# UB8830_Ersatz_005_EAGLE_630.net
KiCad netlist of a schematic drawn in EAGLE
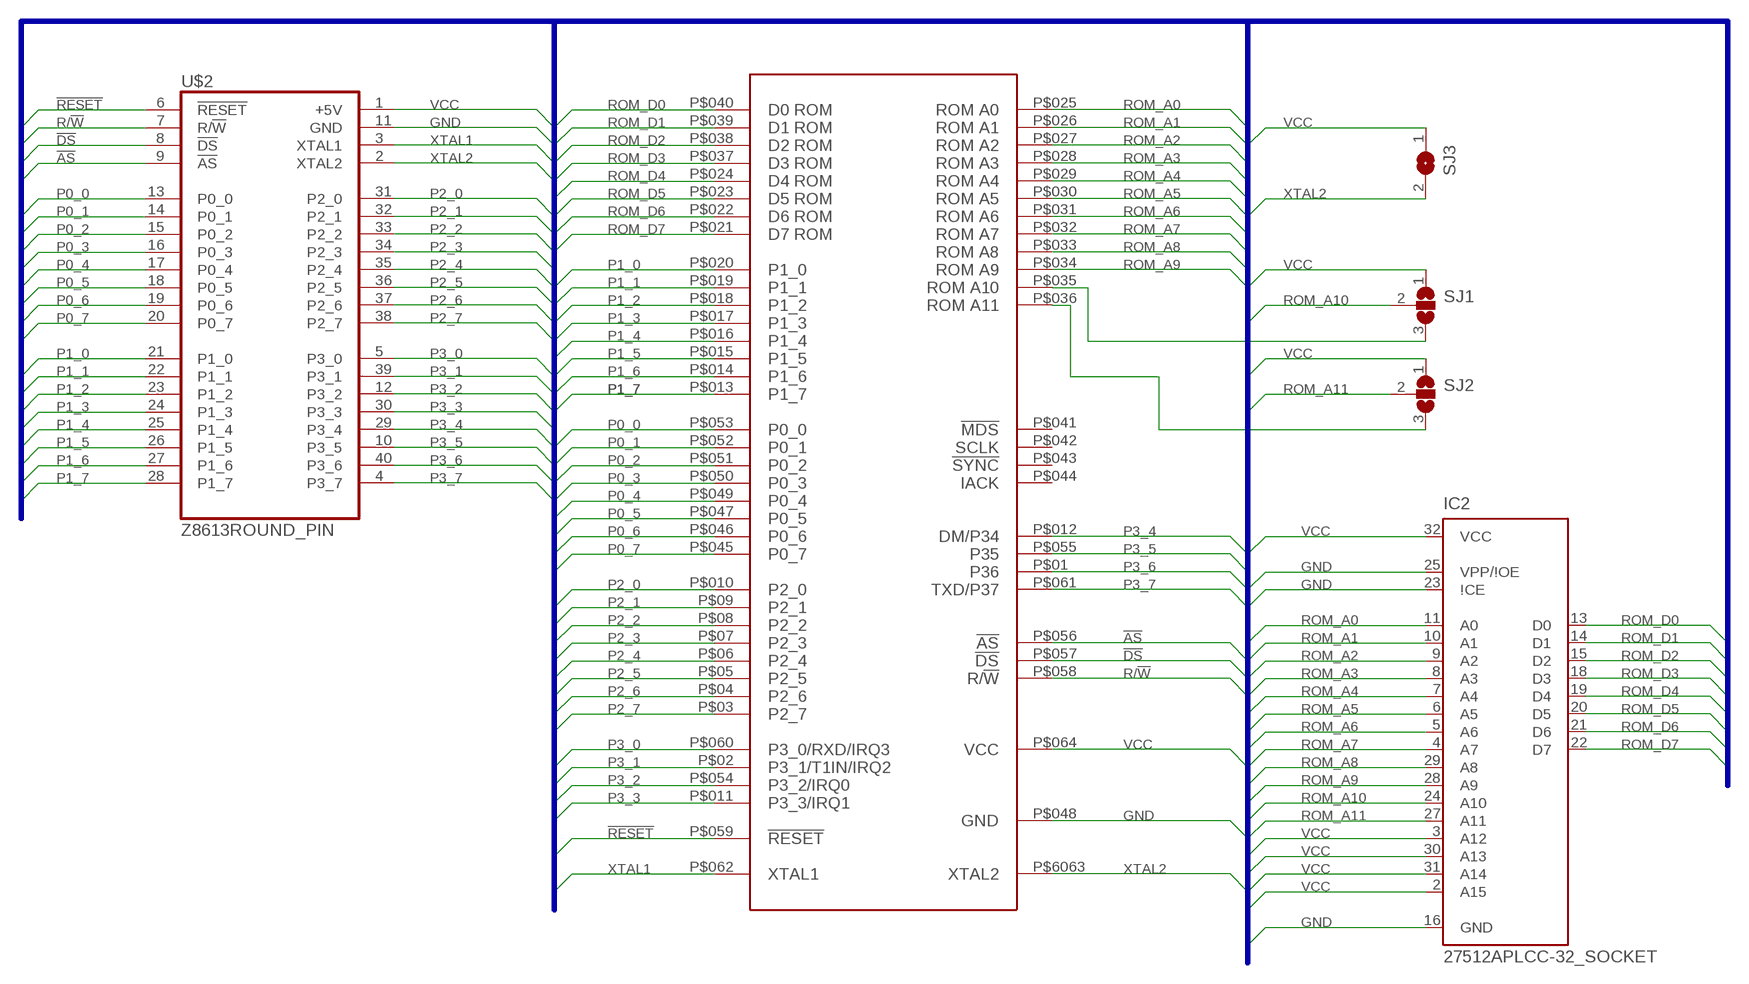
[diagram p0: schematic, sheet 1]

(export (version "E")
  (design (tool "Eeschema 10.0.6"))
  (components
    (comp (ref "IC2")
      (value "27512APLCC-32_SOCKET")
      (footprint "eagle-import:PLCC-32_SOCKET")
      (libsource (lib "eagle-import") (part "27512APLCC-32_SOCKET"))
    )
    (comp (ref "SJ1")
      (value "SJ2WSJ_2B")
      (footprint "eagle-import:SJ_2B")
      (libsource (lib "eagle-import") (part "SJ2WSJ_2B"))
    )
    (comp (ref "SJ2")
      (value "SJ2WSJ_2B")
      (footprint "eagle-import:SJ_2B")
      (libsource (lib "eagle-import") (part "SJ2WSJ_2B"))
    )
    (comp (ref "SJ3") (value "SJ") (footprint "eagle-import:SJ") (libsource (lib "eagle-import") (part "SJ")))
    (comp (ref "U$1")
      (value "UB8821")
      (footprint "eagle-import:QUIT64")
      (libsource (lib "eagle-import") (part "UB8821"))
    )
    (comp (ref "U$2")
      (value "Z8613ROUND_PIN")
      (footprint "eagle-import:DIL40_ROUND")
      (libsource (lib "eagle-import") (part "Z8613ROUND_PIN"))
    )
  )
  (nets
    (net (code "1") (name "/GND") (class "Default")
      (node (ref "IC2") (pin "16") (pinfunction "GND_16") (pintype "power_in"))
      (node (ref "IC2") (pin "23") (pinfunction "\\~{CE}_23") (pintype "input"))
      (node (ref "IC2") (pin "25") (pinfunction "VPP/\\~{OE}_25") (pintype "input"))
      (node (ref "U$1") (pin "P$048") (pinfunction "P$48_P$048") (pintype "bidirectional"))
      (node (ref "U$2") (pin "11") (pinfunction "GND_11") (pintype "power_in"))
    )
    (net (code "2") (name "/P0_0") (class "Default")
      (node (ref "U$1") (pin "P$053") (pinfunction "P$53_P$053") (pintype "bidirectional"))
      (node (ref "U$2") (pin "13") (pinfunction "P0_0_13") (pintype "bidirectional"))
    )
    (net (code "3") (name "/P0_1") (class "Default")
      (node (ref "U$1") (pin "P$052") (pinfunction "P$52_P$052") (pintype "bidirectional"))
      (node (ref "U$2") (pin "14") (pinfunction "P0_1_14") (pintype "bidirectional"))
    )
    (net (code "4") (name "/P0_2") (class "Default")
      (node (ref "U$1") (pin "P$051") (pinfunction "P$51_P$051") (pintype "bidirectional"))
      (node (ref "U$2") (pin "15") (pinfunction "P0_2_15") (pintype "bidirectional"))
    )
    (net (code "5") (name "/P0_3") (class "Default")
      (node (ref "U$1") (pin "P$050") (pinfunction "P$50_P$050") (pintype "bidirectional"))
      (node (ref "U$2") (pin "16") (pinfunction "P0_3_16") (pintype "bidirectional"))
    )
    (net (code "6") (name "/P0_4") (class "Default")
      (node (ref "U$1") (pin "P$049") (pinfunction "P$49_P$049") (pintype "bidirectional"))
      (node (ref "U$2") (pin "17") (pinfunction "P0_4_17") (pintype "bidirectional"))
    )
    (net (code "7") (name "/P0_5") (class "Default")
      (node (ref "U$1") (pin "P$047") (pinfunction "P$47_P$047") (pintype "bidirectional"))
      (node (ref "U$2") (pin "18") (pinfunction "P0_5_18") (pintype "bidirectional"))
    )
    (net (code "8") (name "/P0_6") (class "Default")
      (node (ref "U$1") (pin "P$046") (pinfunction "P$46_P$046") (pintype "bidirectional"))
      (node (ref "U$2") (pin "19") (pinfunction "P0_6_19") (pintype "bidirectional"))
    )
    (net (code "9") (name "/P0_7") (class "Default")
      (node (ref "U$1") (pin "P$045") (pinfunction "P$45_P$045") (pintype "bidirectional"))
      (node (ref "U$2") (pin "20") (pinfunction "P0_7_20") (pintype "bidirectional"))
    )
    (net (code "10") (name "/P1_0") (class "Default")
      (node (ref "U$1") (pin "P$020") (pinfunction "P$20_P$020") (pintype "bidirectional"))
      (node (ref "U$2") (pin "21") (pinfunction "P1_0_21") (pintype "bidirectional"))
    )
    (net (code "11") (name "/P1_1") (class "Default")
      (node (ref "U$1") (pin "P$019") (pinfunction "P$19_P$019") (pintype "bidirectional"))
      (node (ref "U$2") (pin "22") (pinfunction "P1_1_22") (pintype "bidirectional"))
    )
    (net (code "12") (name "/P1_2") (class "Default")
      (node (ref "U$1") (pin "P$018") (pinfunction "P$18_P$018") (pintype "bidirectional"))
      (node (ref "U$2") (pin "23") (pinfunction "P1_2_23") (pintype "bidirectional"))
    )
    (net (code "13") (name "/P1_3") (class "Default")
      (node (ref "U$1") (pin "P$017") (pinfunction "P$17_P$017") (pintype "bidirectional"))
      (node (ref "U$2") (pin "24") (pinfunction "P1_3_24") (pintype "bidirectional"))
    )
    (net (code "14") (name "/P1_4") (class "Default")
      (node (ref "U$1") (pin "P$016") (pinfunction "P$16_P$016") (pintype "bidirectional"))
      (node (ref "U$2") (pin "25") (pinfunction "P1_4_25") (pintype "bidirectional"))
    )
    (net (code "15") (name "/P1_5") (class "Default")
      (node (ref "U$1") (pin "P$015") (pinfunction "P$15_P$015") (pintype "bidirectional"))
      (node (ref "U$2") (pin "26") (pinfunction "P1_5_26") (pintype "bidirectional"))
    )
    (net (code "16") (name "/P1_6") (class "Default")
      (node (ref "U$1") (pin "P$014") (pinfunction "P$14_P$014") (pintype "bidirectional"))
      (node (ref "U$2") (pin "27") (pinfunction "P1_6_27") (pintype "bidirectional"))
    )
    (net (code "17") (name "/P1_7") (class "Default")
      (node (ref "U$1") (pin "P$013") (pinfunction "P$13_P$013") (pintype "bidirectional"))
      (node (ref "U$2") (pin "28") (pinfunction "P1_7_28") (pintype "bidirectional"))
    )
    (net (code "18") (name "/P2_0") (class "Default")
      (node (ref "U$1") (pin "P$010") (pinfunction "P$10_P$010") (pintype "bidirectional"))
      (node (ref "U$2") (pin "31") (pinfunction "P2_0_31") (pintype "bidirectional"))
    )
    (net (code "19") (name "/P2_1") (class "Default")
      (node (ref "U$1") (pin "P$09") (pinfunction "P$9_P$09") (pintype "bidirectional"))
      (node (ref "U$2") (pin "32") (pinfunction "P2_1_32") (pintype "bidirectional"))
    )
    (net (code "20") (name "/P2_2") (class "Default")
      (node (ref "U$1") (pin "P$08") (pinfunction "P$8_P$08") (pintype "bidirectional"))
      (node (ref "U$2") (pin "33") (pinfunction "P2_2_33") (pintype "bidirectional"))
    )
    (net (code "21") (name "/P2_3") (class "Default")
      (node (ref "U$1") (pin "P$07") (pinfunction "P$7_P$07") (pintype "bidirectional"))
      (node (ref "U$2") (pin "34") (pinfunction "P2_3_34") (pintype "bidirectional"))
    )
    (net (code "22") (name "/P2_4") (class "Default")
      (node (ref "U$1") (pin "P$06") (pinfunction "P$6_P$06") (pintype "bidirectional"))
      (node (ref "U$2") (pin "35") (pinfunction "P2_4_35") (pintype "bidirectional"))
    )
    (net (code "23") (name "/P2_5") (class "Default")
      (node (ref "U$1") (pin "P$05") (pinfunction "P$5_P$05") (pintype "bidirectional"))
      (node (ref "U$2") (pin "36") (pinfunction "P2_5_36") (pintype "bidirectional"))
    )
    (net (code "24") (name "/P2_6") (class "Default")
      (node (ref "U$1") (pin "P$04") (pinfunction "P$4_P$04") (pintype "bidirectional"))
      (node (ref "U$2") (pin "37") (pinfunction "P2_6_37") (pintype "bidirectional"))
    )
    (net (code "25") (name "/P2_7") (class "Default")
      (node (ref "U$1") (pin "P$03") (pinfunction "P$3_P$03") (pintype "bidirectional"))
      (node (ref "U$2") (pin "38") (pinfunction "P2_7_38") (pintype "bidirectional"))
    )
    (net (code "26") (name "/P3_0") (class "Default")
      (node (ref "U$1") (pin "P$060") (pinfunction "P$60_P$060") (pintype "bidirectional"))
      (node (ref "U$2") (pin "5") (pinfunction "P3_0_5") (pintype "input"))
    )
    (net (code "27") (name "/P3_1") (class "Default")
      (node (ref "U$1") (pin "P$02") (pinfunction "P$2_P$02") (pintype "bidirectional"))
      (node (ref "U$2") (pin "39") (pinfunction "P3_1_39") (pintype "input"))
    )
    (net (code "28") (name "/P3_2") (class "Default")
      (node (ref "U$1") (pin "P$054") (pinfunction "P$54_P$054") (pintype "bidirectional"))
      (node (ref "U$2") (pin "12") (pinfunction "P3_2_12") (pintype "input"))
    )
    (net (code "29") (name "/P3_3") (class "Default")
      (node (ref "U$1") (pin "P$011") (pinfunction "P$11_P$011") (pintype "bidirectional"))
      (node (ref "U$2") (pin "30") (pinfunction "P3_3_30") (pintype "input"))
    )
    (net (code "30") (name "/P3_4") (class "Default")
      (node (ref "U$1") (pin "P$012") (pinfunction "P$12_P$012") (pintype "bidirectional"))
      (node (ref "U$2") (pin "29") (pinfunction "P3_4_29") (pintype "output"))
    )
    (net (code "31") (name "/P3_5") (class "Default")
      (node (ref "U$1") (pin "P$055") (pinfunction "P$55_P$055") (pintype "bidirectional"))
      (node (ref "U$2") (pin "10") (pinfunction "P3_5_10") (pintype "output"))
    )
    (net (code "32") (name "/P3_6") (class "Default")
      (node (ref "U$1") (pin "P$01") (pinfunction "P$1_P$01") (pintype "bidirectional"))
      (node (ref "U$2") (pin "40") (pinfunction "P3_6_40") (pintype "output"))
    )
    (net (code "33") (name "/P3_7") (class "Default")
      (node (ref "U$1") (pin "P$061") (pinfunction "P$61_P$061") (pintype "bidirectional"))
      (node (ref "U$2") (pin "4") (pinfunction "P3_7_4") (pintype "output"))
    )
    (net (code "34") (name "/ROM_A0") (class "Default")
      (node (ref "IC2") (pin "11") (pinfunction "A0_11") (pintype "input"))
      (node (ref "U$1") (pin "P$025") (pinfunction "P$25_P$025") (pintype "bidirectional"))
    )
    (net (code "35") (name "/ROM_A1") (class "Default")
      (node (ref "IC2") (pin "10") (pinfunction "A1_10") (pintype "input"))
      (node (ref "U$1") (pin "P$026") (pinfunction "P$26_P$026") (pintype "bidirectional"))
    )
    (net (code "36") (name "/ROM_A2") (class "Default")
      (node (ref "IC2") (pin "9") (pinfunction "A2_9") (pintype "input"))
      (node (ref "U$1") (pin "P$027") (pinfunction "P$27_P$027") (pintype "bidirectional"))
    )
    (net (code "37") (name "/ROM_A3") (class "Default")
      (node (ref "IC2") (pin "8") (pinfunction "A3_8") (pintype "input"))
      (node (ref "U$1") (pin "P$028") (pinfunction "P$28_P$028") (pintype "bidirectional"))
    )
    (net (code "38") (name "/ROM_A4") (class "Default")
      (node (ref "IC2") (pin "7") (pinfunction "A4_7") (pintype "input"))
      (node (ref "U$1") (pin "P$029") (pinfunction "P$29_P$029") (pintype "bidirectional"))
    )
    (net (code "39") (name "/ROM_A5") (class "Default")
      (node (ref "IC2") (pin "6") (pinfunction "A5_6") (pintype "input"))
      (node (ref "U$1") (pin "P$030") (pinfunction "P$30_P$030") (pintype "bidirectional"))
    )
    (net (code "40") (name "/ROM_A6") (class "Default")
      (node (ref "IC2") (pin "5") (pinfunction "A6_5") (pintype "input"))
      (node (ref "U$1") (pin "P$031") (pinfunction "P$31_P$031") (pintype "bidirectional"))
    )
    (net (code "41") (name "/ROM_A7") (class "Default")
      (node (ref "IC2") (pin "4") (pinfunction "A7_4") (pintype "input"))
      (node (ref "U$1") (pin "P$032") (pinfunction "P$32_P$032") (pintype "bidirectional"))
    )
    (net (code "42") (name "/ROM_A8") (class "Default")
      (node (ref "IC2") (pin "29") (pinfunction "A8_29") (pintype "input"))
      (node (ref "U$1") (pin "P$033") (pinfunction "P$33_P$033") (pintype "bidirectional"))
    )
    (net (code "43") (name "/ROM_A9") (class "Default")
      (node (ref "IC2") (pin "28") (pinfunction "A9_28") (pintype "input"))
      (node (ref "U$1") (pin "P$034") (pinfunction "P$34_P$034") (pintype "bidirectional"))
    )
    (net (code "44") (name "/ROM_A10") (class "Default")
      (node (ref "IC2") (pin "24") (pinfunction "A10_24") (pintype "input"))
      (node (ref "SJ1") (pin "2") (pinfunction "2_2") (pintype "passive"))
    )
    (net (code "45") (name "/ROM_A11") (class "Default")
      (node (ref "IC2") (pin "27") (pinfunction "A11_27") (pintype "input"))
      (node (ref "SJ2") (pin "2") (pinfunction "2_2") (pintype "passive"))
    )
    (net (code "46") (name "/ROM_D0") (class "Default")
      (node (ref "IC2") (pin "13") (pinfunction "D0_13") (pintype "tri_state"))
      (node (ref "U$1") (pin "P$040") (pinfunction "P$40_P$040") (pintype "output"))
    )
    (net (code "47") (name "/ROM_D1") (class "Default")
      (node (ref "IC2") (pin "14") (pinfunction "D1_14") (pintype "tri_state"))
      (node (ref "U$1") (pin "P$039") (pinfunction "P$39_P$039") (pintype "output"))
    )
    (net (code "48") (name "/ROM_D2") (class "Default")
      (node (ref "IC2") (pin "15") (pinfunction "D2_15") (pintype "tri_state"))
      (node (ref "U$1") (pin "P$038") (pinfunction "P$38_P$038") (pintype "output"))
    )
    (net (code "49") (name "/ROM_D3") (class "Default")
      (node (ref "IC2") (pin "18") (pinfunction "D3_18") (pintype "tri_state"))
      (node (ref "U$1") (pin "P$037") (pinfunction "P$37_P$037") (pintype "output"))
    )
    (net (code "50") (name "/ROM_D4") (class "Default")
      (node (ref "IC2") (pin "19") (pinfunction "D4_19") (pintype "tri_state"))
      (node (ref "U$1") (pin "P$024") (pinfunction "P$24_P$024") (pintype "output"))
    )
    (net (code "51") (name "/ROM_D5") (class "Default")
      (node (ref "IC2") (pin "20") (pinfunction "D5_20") (pintype "tri_state"))
      (node (ref "U$1") (pin "P$023") (pinfunction "P$23_P$023") (pintype "output"))
    )
    (net (code "52") (name "/ROM_D6") (class "Default")
      (node (ref "IC2") (pin "21") (pinfunction "D6_21") (pintype "tri_state"))
      (node (ref "U$1") (pin "P$022") (pinfunction "P$22_P$022") (pintype "output"))
    )
    (net (code "53") (name "/ROM_D7") (class "Default")
      (node (ref "IC2") (pin "22") (pinfunction "D7_22") (pintype "tri_state"))
      (node (ref "U$1") (pin "P$021") (pinfunction "P$21_P$021") (pintype "output"))
    )
    (net (code "54") (name "/R{slash}~{W}") (class "Default")
      (node (ref "U$1") (pin "P$058") (pinfunction "P$58_P$058") (pintype "bidirectional"))
      (node (ref "U$2") (pin "7") (pinfunction "R/~{W}_7") (pintype "output"))
    )
    (net (code "55") (name "/VCC") (class "Default")
      (node (ref "IC2") (pin "2") (pinfunction "A15_2") (pintype "input"))
      (node (ref "IC2") (pin "3") (pinfunction "A12_3") (pintype "input"))
      (node (ref "IC2") (pin "30") (pinfunction "A13_30") (pintype "input"))
      (node (ref "IC2") (pin "31") (pinfunction "A14_31") (pintype "input"))
      (node (ref "IC2") (pin "32") (pinfunction "VCC_32") (pintype "power_in"))
      (node (ref "SJ1") (pin "1") (pinfunction "1_1") (pintype "passive"))
      (node (ref "SJ2") (pin "1") (pinfunction "1_1") (pintype "passive"))
      (node (ref "SJ3") (pin "1") (pinfunction "1_1") (pintype "passive"))
      (node (ref "U$1") (pin "P$064") (pinfunction "P$64_P$064") (pintype "bidirectional"))
      (node (ref "U$2") (pin "1") (pinfunction "+5V_1") (pintype "power_in"))
    )
    (net (code "56") (name "/XTAL1") (class "Default")
      (node (ref "U$1") (pin "P$062") (pinfunction "P$62_P$062") (pintype "bidirectional"))
      (node (ref "U$2") (pin "3") (pinfunction "XTAL1_3") (pintype "input"))
    )
    (net (code "57") (name "/XTAL2") (class "Default")
      (node (ref "SJ3") (pin "2") (pinfunction "2_2") (pintype "passive"))
      (node (ref "U$1") (pin "P$6063") (pinfunction "P$63_P$6063") (pintype "bidirectional"))
      (node (ref "U$2") (pin "2") (pinfunction "XTAL2_2") (pintype "output"))
    )
    (net (code "58") (name "/~{AS}") (class "Default")
      (node (ref "U$1") (pin "P$056") (pinfunction "P$56_P$056") (pintype "bidirectional"))
      (node (ref "U$2") (pin "9") (pinfunction "~{AS}_9") (pintype "output"))
    )
    (net (code "59") (name "/~{DS}") (class "Default")
      (node (ref "U$1") (pin "P$057") (pinfunction "P$57_P$057") (pintype "bidirectional"))
      (node (ref "U$2") (pin "8") (pinfunction "~{DS}_8") (pintype "output"))
    )
    (net (code "60") (name "/~{RESET}") (class "Default")
      (node (ref "U$1") (pin "P$059") (pinfunction "P$59_P$059") (pintype "bidirectional"))
      (node (ref "U$2") (pin "6") (pinfunction "~{RESET}_6") (pintype "input"))
    )
    (net (code "61") (name "Net-(U$1-P$35)") (class "Default")
      (node (ref "SJ1") (pin "3") (pinfunction "3_3") (pintype "passive"))
      (node (ref "U$1") (pin "P$035") (pinfunction "P$35_P$035") (pintype "bidirectional"))
    )
    (net (code "62") (name "Net-(U$1-P$36)") (class "Default")
      (node (ref "SJ2") (pin "3") (pinfunction "3_3") (pintype "passive"))
      (node (ref "U$1") (pin "P$036") (pinfunction "P$36_P$036") (pintype "bidirectional"))
    )
    (net (code "63") (name "unconnected-(U$1-P$41-PadP$041)") (class "Default")
      (node (ref "U$1") (pin "P$041") (pinfunction "P$41_P$041") (pintype "bidirectional"))
    )
    (net (code "64") (name "unconnected-(U$1-P$42-PadP$042)") (class "Default")
      (node (ref "U$1") (pin "P$042") (pinfunction "P$42_P$042") (pintype "bidirectional"))
    )
    (net (code "65") (name "unconnected-(U$1-P$43-PadP$043)") (class "Default")
      (node (ref "U$1") (pin "P$043") (pinfunction "P$43_P$043") (pintype "bidirectional"))
    )
    (net (code "66") (name "unconnected-(U$1-P$44-PadP$044)") (class "Default")
      (node (ref "U$1") (pin "P$044") (pinfunction "P$44_P$044") (pintype "bidirectional"))
    )
  )
)
